# ButterWorth_8th_order_Filter.net
KiCad netlist of a schematic drawn in Altium Designer
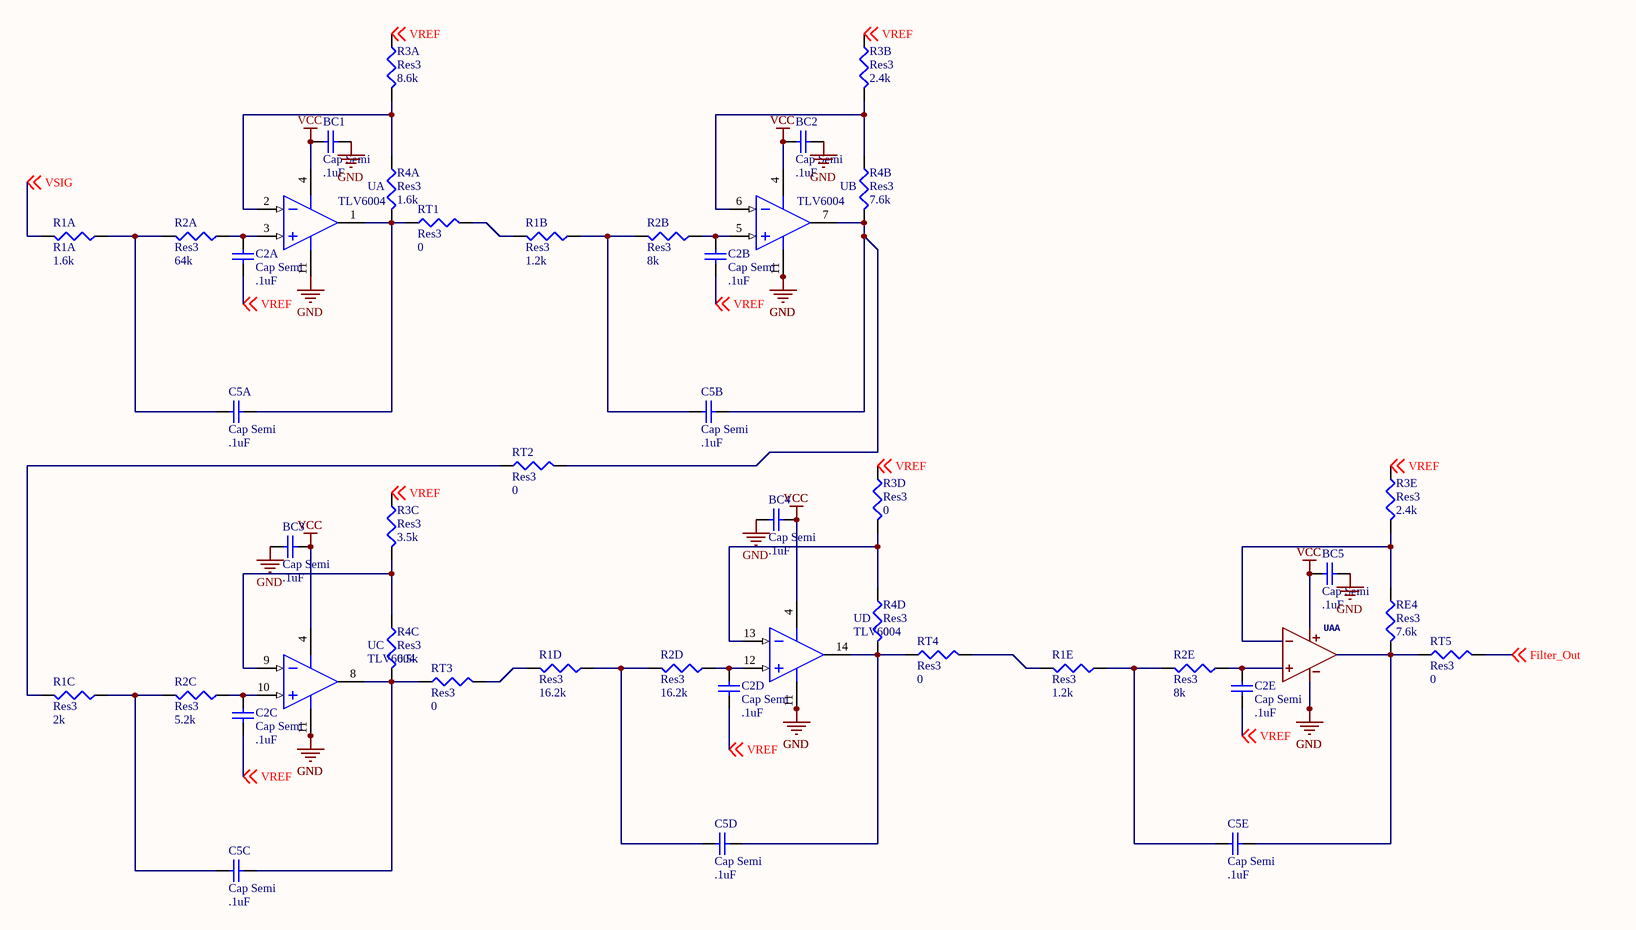
[diagram p0: ButterWorth_8th_order_Filter.SchDoc]

(export (version "E")
  (design (tool "Eeschema 10.0.6"))
  (components
    (comp (ref "BC1")
      (value "Cap Semi")
      (footprint "1608[0603]")
      (description "Capacitor (Semiconductor SIM Model)")
      (fields (field (name "ALTIUM_VALUE") ".1uF") (field (name "PUBLISHER") "Altium Limited"))
      (libsource (lib "Miscellaneous Devices") (part "Cap Semi"))
    )
    (comp (ref "BC2")
      (value "Cap Semi")
      (footprint "1608[0603]")
      (description "Capacitor (Semiconductor SIM Model)")
      (fields (field (name "ALTIUM_VALUE") ".1uF") (field (name "PUBLISHER") "Altium Limited"))
      (libsource (lib "Miscellaneous Devices") (part "Cap Semi"))
    )
    (comp (ref "BC3")
      (value "Cap Semi")
      (footprint "1608[0603]")
      (description "Capacitor (Semiconductor SIM Model)")
      (fields (field (name "ALTIUM_VALUE") ".1uF") (field (name "PUBLISHER") "Altium Limited"))
      (libsource (lib "Miscellaneous Devices") (part "Cap Semi"))
    )
    (comp (ref "BC4")
      (value "Cap Semi")
      (footprint "1608[0603]")
      (description "Capacitor (Semiconductor SIM Model)")
      (fields (field (name "ALTIUM_VALUE") ".1uF") (field (name "PUBLISHER") "Altium Limited"))
      (libsource (lib "Miscellaneous Devices") (part "Cap Semi"))
    )
    (comp (ref "BC5")
      (value "Cap Semi")
      (footprint "1608[0603]")
      (description "Capacitor (Semiconductor SIM Model)")
      (fields (field (name "ALTIUM_VALUE") ".1uF") (field (name "PUBLISHER") "Altium Limited"))
      (libsource (lib "Miscellaneous Devices") (part "Cap Semi"))
    )
    (comp (ref "C2A")
      (value "Cap Semi")
      (footprint "1608[0603]")
      (description "Capacitor (Semiconductor SIM Model)")
      (fields (field (name "ALTIUM_VALUE") ".1uF") (field (name "PUBLISHER") "Altium Limited"))
      (libsource (lib "Miscellaneous Devices") (part "Cap Semi"))
    )
    (comp (ref "C2B")
      (value "Cap Semi")
      (footprint "1608[0603]")
      (description "Capacitor (Semiconductor SIM Model)")
      (fields (field (name "ALTIUM_VALUE") ".1uF") (field (name "PUBLISHER") "Altium Limited"))
      (libsource (lib "Miscellaneous Devices") (part "Cap Semi"))
    )
    (comp (ref "C2C")
      (value "Cap Semi")
      (footprint "1608[0603]")
      (description "Capacitor (Semiconductor SIM Model)")
      (fields (field (name "ALTIUM_VALUE") ".1uF") (field (name "PUBLISHER") "Altium Limited"))
      (libsource (lib "Miscellaneous Devices") (part "Cap Semi"))
    )
    (comp (ref "C2D")
      (value "Cap Semi")
      (footprint "1608[0603]")
      (description "Capacitor (Semiconductor SIM Model)")
      (fields (field (name "ALTIUM_VALUE") ".1uF") (field (name "PUBLISHER") "Altium Limited"))
      (libsource (lib "Miscellaneous Devices") (part "Cap Semi"))
    )
    (comp (ref "C2E")
      (value "Cap Semi")
      (footprint "1608[0603]")
      (description "Capacitor (Semiconductor SIM Model)")
      (fields (field (name "ALTIUM_VALUE") ".1uF") (field (name "PUBLISHER") "Altium Limited"))
      (libsource (lib "Miscellaneous Devices") (part "Cap Semi"))
    )
    (comp (ref "C5A")
      (value "Cap Semi")
      (footprint "C1206")
      (description "Capacitor (Semiconductor SIM Model)")
      (fields (field (name "ALTIUM_VALUE") ".1uF") (field (name "PUBLISHER") "Altium Limited"))
      (libsource (lib "Miscellaneous Devices") (part "Cap Semi"))
    )
    (comp (ref "C5B")
      (value "Cap Semi")
      (footprint "C1206")
      (description "Capacitor (Semiconductor SIM Model)")
      (fields (field (name "ALTIUM_VALUE") ".1uF") (field (name "PUBLISHER") "Altium Limited"))
      (libsource (lib "Miscellaneous Devices") (part "Cap Semi"))
    )
    (comp (ref "C5C")
      (value "Cap Semi")
      (footprint "C1206")
      (description "Capacitor (Semiconductor SIM Model)")
      (fields (field (name "ALTIUM_VALUE") ".1uF") (field (name "PUBLISHER") "Altium Limited"))
      (libsource (lib "Miscellaneous Devices") (part "Cap Semi"))
    )
    (comp (ref "C5D")
      (value "Cap Semi")
      (footprint "C1206")
      (description "Capacitor (Semiconductor SIM Model)")
      (fields (field (name "ALTIUM_VALUE") ".1uF") (field (name "PUBLISHER") "Altium Limited"))
      (libsource (lib "Miscellaneous Devices") (part "Cap Semi"))
    )
    (comp (ref "C5E")
      (value "Cap Semi")
      (footprint "C1206")
      (description "Capacitor (Semiconductor SIM Model)")
      (fields (field (name "ALTIUM_VALUE") ".1uF") (field (name "PUBLISHER") "Altium Limited"))
      (libsource (lib "Miscellaneous Devices") (part "Cap Semi"))
    )
    (comp (ref "R1A")
      (value "R1A")
      (footprint "J1-0603")
      (description "Resistor")
      (fields (field (name "ALTIUM_VALUE") "1.6k") (field (name "PUBLISHER") "Altium Limited"))
      (libsource (lib "Miscellaneous Devices") (part "Res3"))
    )
    (comp (ref "R1B")
      (value "Res3")
      (footprint "J1-0603")
      (description "Resistor")
      (fields (field (name "ALTIUM_VALUE") "1.2k") (field (name "PUBLISHER") "Altium Limited"))
      (libsource (lib "Miscellaneous Devices") (part "Res3"))
    )
    (comp (ref "R1C")
      (value "Res3")
      (footprint "J1-0603")
      (description "Resistor")
      (fields (field (name "ALTIUM_VALUE") "2k") (field (name "PUBLISHER") "Altium Limited"))
      (libsource (lib "Miscellaneous Devices") (part "Res3"))
    )
    (comp (ref "R1D")
      (value "Res3")
      (footprint "J1-0603")
      (description "Resistor")
      (fields (field (name "ALTIUM_VALUE") "16.2k") (field (name "PUBLISHER") "Altium Limited"))
      (libsource (lib "Miscellaneous Devices") (part "Res3"))
    )
    (comp (ref "R1E")
      (value "Res3")
      (footprint "J1-0603")
      (description "Resistor")
      (fields (field (name "ALTIUM_VALUE") "1.2k") (field (name "PUBLISHER") "Altium Limited"))
      (libsource (lib "Miscellaneous Devices") (part "Res3"))
    )
    (comp (ref "R2A")
      (value "Res3")
      (footprint "J1-0603")
      (description "Resistor")
      (fields (field (name "ALTIUM_VALUE") "64k") (field (name "PUBLISHER") "Altium Limited"))
      (libsource (lib "Miscellaneous Devices") (part "Res3"))
    )
    (comp (ref "R2B")
      (value "Res3")
      (footprint "J1-0603")
      (description "Resistor")
      (fields (field (name "ALTIUM_VALUE") "8k") (field (name "PUBLISHER") "Altium Limited"))
      (libsource (lib "Miscellaneous Devices") (part "Res3"))
    )
    (comp (ref "R2C")
      (value "Res3")
      (footprint "J1-0603")
      (description "Resistor")
      (fields (field (name "ALTIUM_VALUE") "5.2k") (field (name "PUBLISHER") "Altium Limited"))
      (libsource (lib "Miscellaneous Devices") (part "Res3"))
    )
    (comp (ref "R2D")
      (value "Res3")
      (footprint "J1-0603")
      (description "Resistor")
      (fields (field (name "ALTIUM_VALUE") "16.2k") (field (name "PUBLISHER") "Altium Limited"))
      (libsource (lib "Miscellaneous Devices") (part "Res3"))
    )
    (comp (ref "R2E")
      (value "Res3")
      (footprint "J1-0603")
      (description "Resistor")
      (fields (field (name "ALTIUM_VALUE") "8k") (field (name "PUBLISHER") "Altium Limited"))
      (libsource (lib "Miscellaneous Devices") (part "Res3"))
    )
    (comp (ref "R3A")
      (value "Res3")
      (footprint "J1-0603")
      (description "Resistor")
      (fields (field (name "ALTIUM_VALUE") "8.6k") (field (name "PUBLISHER") "Altium Limited"))
      (libsource (lib "Miscellaneous Devices") (part "Res3"))
    )
    (comp (ref "R3B")
      (value "Res3")
      (footprint "J1-0603")
      (description "Resistor")
      (fields (field (name "ALTIUM_VALUE") "2.4k") (field (name "PUBLISHER") "Altium Limited"))
      (libsource (lib "Miscellaneous Devices") (part "Res3"))
    )
    (comp (ref "R3C")
      (value "Res3")
      (footprint "J1-0603")
      (description "Resistor")
      (fields (field (name "ALTIUM_VALUE") "3.5k") (field (name "PUBLISHER") "Altium Limited"))
      (libsource (lib "Miscellaneous Devices") (part "Res3"))
    )
    (comp (ref "R3D")
      (value "Res3")
      (footprint "J1-0603")
      (description "Resistor")
      (fields (field (name "ALTIUM_VALUE") "0") (field (name "PUBLISHER") "Altium Limited"))
      (libsource (lib "Miscellaneous Devices") (part "Res3"))
    )
    (comp (ref "R3E")
      (value "Res3")
      (footprint "J1-0603")
      (description "Resistor")
      (fields (field (name "ALTIUM_VALUE") "2.4k") (field (name "PUBLISHER") "Altium Limited"))
      (libsource (lib "Miscellaneous Devices") (part "Res3"))
    )
    (comp (ref "R4A")
      (value "Res3")
      (footprint "J1-0603")
      (description "Resistor")
      (fields (field (name "ALTIUM_VALUE") "1.6k") (field (name "PUBLISHER") "Altium Limited"))
      (libsource (lib "Miscellaneous Devices") (part "Res3"))
    )
    (comp (ref "R4B")
      (value "Res3")
      (footprint "J1-0603")
      (description "Resistor")
      (fields (field (name "ALTIUM_VALUE") "7.6k") (field (name "PUBLISHER") "Altium Limited"))
      (libsource (lib "Miscellaneous Devices") (part "Res3"))
    )
    (comp (ref "R4C")
      (value "Res3")
      (footprint "J1-0603")
      (description "Resistor")
      (fields (field (name "ALTIUM_VALUE") "6.5k") (field (name "PUBLISHER") "Altium Limited"))
      (libsource (lib "Miscellaneous Devices") (part "Res3"))
    )
    (comp (ref "R4D")
      (value "Res3")
      (footprint "J1-0603")
      (description "Resistor")
      (fields (field (name "ALTIUM_VALUE") "0") (field (name "PUBLISHER") "Altium Limited"))
      (libsource (lib "Miscellaneous Devices") (part "Res3"))
    )
    (comp (ref "RE4")
      (value "Res3")
      (footprint "J1-0603")
      (description "Resistor")
      (fields (field (name "ALTIUM_VALUE") "7.6k") (field (name "PUBLISHER") "Altium Limited"))
      (libsource (lib "Miscellaneous Devices") (part "Res3"))
    )
    (comp (ref "RT1")
      (value "Res3")
      (footprint "J1-0603")
      (description "Resistor")
      (fields (field (name "ALTIUM_VALUE") "0") (field (name "PUBLISHER") "Altium Limited"))
      (libsource (lib "Miscellaneous Devices") (part "Res3"))
    )
    (comp (ref "RT2")
      (value "Res3")
      (footprint "J1-0603")
      (description "Resistor")
      (fields (field (name "ALTIUM_VALUE") "0") (field (name "PUBLISHER") "Altium Limited"))
      (libsource (lib "Miscellaneous Devices") (part "Res3"))
    )
    (comp (ref "RT3")
      (value "Res3")
      (footprint "J1-0603")
      (description "Resistor")
      (fields (field (name "ALTIUM_VALUE") "0") (field (name "PUBLISHER") "Altium Limited"))
      (libsource (lib "Miscellaneous Devices") (part "Res3"))
    )
    (comp (ref "RT4")
      (value "Res3")
      (footprint "J1-0603")
      (description "Resistor")
      (fields (field (name "ALTIUM_VALUE") "0") (field (name "PUBLISHER") "Altium Limited"))
      (libsource (lib "Miscellaneous Devices") (part "Res3"))
    )
    (comp (ref "RT5")
      (value "Res3")
      (footprint "J1-0603")
      (description "Resistor")
      (fields (field (name "ALTIUM_VALUE") "0") (field (name "PUBLISHER") "Altium Limited"))
      (libsource (lib "Miscellaneous Devices") (part "Res3"))
    )
    (comp (ref "U")
      (value "TLV6004")
      (footprint "SOP65P640X120-14N")
      (description "Low Power Quad Differential Comparator")
      (fields (field (name "PUBLISHER") "Altium Limited"))
      (libsource (lib "TI Analog Comparator") (part "LP2901D"))
    )
    (comp (ref "UAA")
      (value "Universal Opamp model that allows 4 different levels of simulation accuracy.  See ./examples/Educational/UniversalOpamp2.asc for details.  En and in are equivalent voltage and current noises.  Enk and ink are the respective corner frequencies.  Phimargin is used to set the 2nd pole or delay to the approximate phase margin for level.3a and level.3b.  This version uses the new, experimental level 2 switch as the output devices.")
      (footprint "SOT95P280X100-5N")
      (fields (field (name "LIBRARYNAME") "Opamps"))
      (libsource (lib "Opamps") (part "UNIVERSALOPAMP2"))
    )
  )
  (nets
    (net (code "1") (name "Filter_Out") (class "Default")
      (node (ref "RT5") (pin "1") (pinfunction "1_1") (pintype "passive"))
    )
    (net (code "2") (name "GND") (class "Default")
      (node (ref "BC1") (pin "1") (pinfunction "1_1") (pintype "passive"))
      (node (ref "BC2") (pin "1") (pinfunction "1_1") (pintype "passive"))
      (node (ref "BC3") (pin "2") (pinfunction "2_2") (pintype "passive"))
      (node (ref "BC4") (pin "2") (pinfunction "2_2") (pintype "passive"))
      (node (ref "BC5") (pin "1") (pinfunction "1_1") (pintype "passive"))
      (node (ref "U") (pin "11") (pinfunction "V-_11") (pintype "power_in"))
      (node (ref "UAA") (pin "2") (pinfunction "V-_2") (pintype "power_in"))
    )
    (net (code "3") (name "Net-(C5A-Pad2)") (class "Default")
      (node (ref "C5A") (pin "2") (pinfunction "2_2") (pintype "passive"))
      (node (ref "R1A") (pin "2") (pinfunction "2_2") (pintype "passive"))
      (node (ref "R2A") (pin "1") (pinfunction "1_1") (pintype "passive"))
    )
    (net (code "4") (name "Net-(C5B-Pad2)") (class "Default")
      (node (ref "C5B") (pin "2") (pinfunction "2_2") (pintype "passive"))
      (node (ref "R1B") (pin "2") (pinfunction "2_2") (pintype "passive"))
      (node (ref "R2B") (pin "1") (pinfunction "1_1") (pintype "passive"))
    )
    (net (code "5") (name "Net-(C5C-Pad2)") (class "Default")
      (node (ref "C5C") (pin "2") (pinfunction "2_2") (pintype "passive"))
      (node (ref "R1C") (pin "2") (pinfunction "2_2") (pintype "passive"))
      (node (ref "R2C") (pin "1") (pinfunction "1_1") (pintype "passive"))
    )
    (net (code "6") (name "Net-(C5D-Pad2)") (class "Default")
      (node (ref "C5D") (pin "2") (pinfunction "2_2") (pintype "passive"))
      (node (ref "R1D") (pin "2") (pinfunction "2_2") (pintype "passive"))
      (node (ref "R2D") (pin "1") (pinfunction "1_1") (pintype "passive"))
    )
    (net (code "7") (name "Net-(C5E-Pad2)") (class "Default")
      (node (ref "C5E") (pin "2") (pinfunction "2_2") (pintype "passive"))
      (node (ref "R1E") (pin "2") (pinfunction "2_2") (pintype "passive"))
      (node (ref "R2E") (pin "1") (pinfunction "1_1") (pintype "passive"))
    )
    (net (code "8") (name "Net-(R1B-Pad1)") (class "Default")
      (node (ref "R1B") (pin "1") (pinfunction "1_1") (pintype "passive"))
      (node (ref "RT1") (pin "1") (pinfunction "1_1") (pintype "passive"))
    )
    (net (code "9") (name "Net-(R1C-Pad1)") (class "Default")
      (node (ref "R1C") (pin "1") (pinfunction "1_1") (pintype "passive"))
      (node (ref "RT2") (pin "2") (pinfunction "2_2") (pintype "passive"))
    )
    (net (code "10") (name "Net-(R1D-Pad1)") (class "Default")
      (node (ref "R1D") (pin "1") (pinfunction "1_1") (pintype "passive"))
      (node (ref "RT3") (pin "1") (pinfunction "1_1") (pintype "passive"))
    )
    (net (code "11") (name "Net-(R1E-Pad1)") (class "Default")
      (node (ref "R1E") (pin "1") (pinfunction "1_1") (pintype "passive"))
      (node (ref "RT4") (pin "1") (pinfunction "1_1") (pintype "passive"))
    )
    (net (code "12") (name "Net-(UA-IN+)") (class "Default")
      (node (ref "C2A") (pin "2") (pinfunction "2_2") (pintype "passive"))
      (node (ref "R2A") (pin "2") (pinfunction "2_2") (pintype "passive"))
      (node (ref "U") (pin "3") (pinfunction "IN+_3") (pintype "input"))
    )
    (net (code "13") (name "Net-(UA-IN-)") (class "Default")
      (node (ref "R3A") (pin "1") (pinfunction "1_1") (pintype "passive"))
      (node (ref "R4A") (pin "2") (pinfunction "2_2") (pintype "passive"))
      (node (ref "U") (pin "2") (pinfunction "IN-_2") (pintype "input"))
    )
    (net (code "14") (name "Net-(UA-OUT)") (class "Default")
      (node (ref "C5A") (pin "1") (pinfunction "1_1") (pintype "passive"))
      (node (ref "R4A") (pin "1") (pinfunction "1_1") (pintype "passive"))
      (node (ref "RT1") (pin "2") (pinfunction "2_2") (pintype "passive"))
      (node (ref "U") (pin "1") (pinfunction "OUT_1") (pintype "open_collector"))
    )
    (net (code "15") (name "Net-(UAA-IN+)") (class "Default")
      (node (ref "C2E") (pin "2") (pinfunction "2_2") (pintype "passive"))
      (node (ref "R2E") (pin "2") (pinfunction "2_2") (pintype "passive"))
      (node (ref "UAA") (pin "3") (pinfunction "IN+_3") (pintype "input"))
    )
    (net (code "16") (name "Net-(UAA-IN-)") (class "Default")
      (node (ref "R3E") (pin "1") (pinfunction "1_1") (pintype "passive"))
      (node (ref "RE4") (pin "2") (pinfunction "2_2") (pintype "passive"))
      (node (ref "UAA") (pin "4") (pinfunction "IN-_4") (pintype "input"))
    )
    (net (code "17") (name "Net-(UAA-OUT)") (class "Default")
      (node (ref "C5E") (pin "1") (pinfunction "1_1") (pintype "passive"))
      (node (ref "RE4") (pin "1") (pinfunction "1_1") (pintype "passive"))
      (node (ref "RT5") (pin "2") (pinfunction "2_2") (pintype "passive"))
      (node (ref "UAA") (pin "1") (pinfunction "OUT_1") (pintype "output"))
    )
    (net (code "18") (name "Net-(UB-IN+)") (class "Default")
      (node (ref "C2B") (pin "2") (pinfunction "2_2") (pintype "passive"))
      (node (ref "R2B") (pin "2") (pinfunction "2_2") (pintype "passive"))
      (node (ref "U") (pin "5") (pinfunction "IN+_5") (pintype "input"))
    )
    (net (code "19") (name "Net-(UB-IN-)") (class "Default")
      (node (ref "R3B") (pin "1") (pinfunction "1_1") (pintype "passive"))
      (node (ref "R4B") (pin "2") (pinfunction "2_2") (pintype "passive"))
      (node (ref "U") (pin "6") (pinfunction "IN-_6") (pintype "input"))
    )
    (net (code "20") (name "Net-(UB-OUT)") (class "Default")
      (node (ref "C5B") (pin "1") (pinfunction "1_1") (pintype "passive"))
      (node (ref "R4B") (pin "1") (pinfunction "1_1") (pintype "passive"))
      (node (ref "RT2") (pin "1") (pinfunction "1_1") (pintype "passive"))
      (node (ref "U") (pin "7") (pinfunction "OUT_7") (pintype "open_collector"))
    )
    (net (code "21") (name "Net-(UC-IN+)") (class "Default")
      (node (ref "C2C") (pin "2") (pinfunction "2_2") (pintype "passive"))
      (node (ref "R2C") (pin "2") (pinfunction "2_2") (pintype "passive"))
      (node (ref "U") (pin "10") (pinfunction "IN+_10") (pintype "input"))
    )
    (net (code "22") (name "Net-(UC-IN-)") (class "Default")
      (node (ref "R3C") (pin "1") (pinfunction "1_1") (pintype "passive"))
      (node (ref "R4C") (pin "2") (pinfunction "2_2") (pintype "passive"))
      (node (ref "U") (pin "9") (pinfunction "IN-_9") (pintype "input"))
    )
    (net (code "23") (name "Net-(UC-OUT)") (class "Default")
      (node (ref "C5C") (pin "1") (pinfunction "1_1") (pintype "passive"))
      (node (ref "R4C") (pin "1") (pinfunction "1_1") (pintype "passive"))
      (node (ref "RT3") (pin "2") (pinfunction "2_2") (pintype "passive"))
      (node (ref "U") (pin "8") (pinfunction "OUT_8") (pintype "open_collector"))
    )
    (net (code "24") (name "Net-(UD-IN+)") (class "Default")
      (node (ref "C2D") (pin "2") (pinfunction "2_2") (pintype "passive"))
      (node (ref "R2D") (pin "2") (pinfunction "2_2") (pintype "passive"))
      (node (ref "U") (pin "12") (pinfunction "IN+_12") (pintype "input"))
    )
    (net (code "25") (name "Net-(UD-IN-)") (class "Default")
      (node (ref "R3D") (pin "1") (pinfunction "1_1") (pintype "passive"))
      (node (ref "R4D") (pin "2") (pinfunction "2_2") (pintype "passive"))
      (node (ref "U") (pin "13") (pinfunction "IN-_13") (pintype "input"))
    )
    (net (code "26") (name "Net-(UD-OUT)") (class "Default")
      (node (ref "C5D") (pin "1") (pinfunction "1_1") (pintype "passive"))
      (node (ref "R4D") (pin "1") (pinfunction "1_1") (pintype "passive"))
      (node (ref "RT4") (pin "2") (pinfunction "2_2") (pintype "passive"))
      (node (ref "U") (pin "14") (pinfunction "OUT_14") (pintype "open_collector"))
    )
    (net (code "27") (name "VCC") (class "Default")
      (node (ref "BC1") (pin "2") (pinfunction "2_2") (pintype "passive"))
      (node (ref "BC2") (pin "2") (pinfunction "2_2") (pintype "passive"))
      (node (ref "BC3") (pin "1") (pinfunction "1_1") (pintype "passive"))
      (node (ref "BC4") (pin "1") (pinfunction "1_1") (pintype "passive"))
      (node (ref "BC5") (pin "2") (pinfunction "2_2") (pintype "passive"))
      (node (ref "U") (pin "4") (pinfunction "V+_4") (pintype "power_in"))
      (node (ref "UAA") (pin "5") (pinfunction "V+_5") (pintype "power_in"))
    )
    (net (code "28") (name "VREF") (class "Default")
      (node (ref "C2A") (pin "1") (pinfunction "1_1") (pintype "passive"))
      (node (ref "C2B") (pin "1") (pinfunction "1_1") (pintype "passive"))
      (node (ref "C2C") (pin "1") (pinfunction "1_1") (pintype "passive"))
      (node (ref "C2D") (pin "1") (pinfunction "1_1") (pintype "passive"))
      (node (ref "C2E") (pin "1") (pinfunction "1_1") (pintype "passive"))
      (node (ref "R3A") (pin "2") (pinfunction "2_2") (pintype "passive"))
      (node (ref "R3B") (pin "2") (pinfunction "2_2") (pintype "passive"))
      (node (ref "R3C") (pin "2") (pinfunction "2_2") (pintype "passive"))
      (node (ref "R3D") (pin "2") (pinfunction "2_2") (pintype "passive"))
      (node (ref "R3E") (pin "2") (pinfunction "2_2") (pintype "passive"))
    )
    (net (code "29") (name "VSIG") (class "Default")
      (node (ref "R1A") (pin "1") (pinfunction "1_1") (pintype "passive"))
    )
  )
)
